# MCU_IMU.net
KiCad netlist of a schematic drawn in Altium Designer
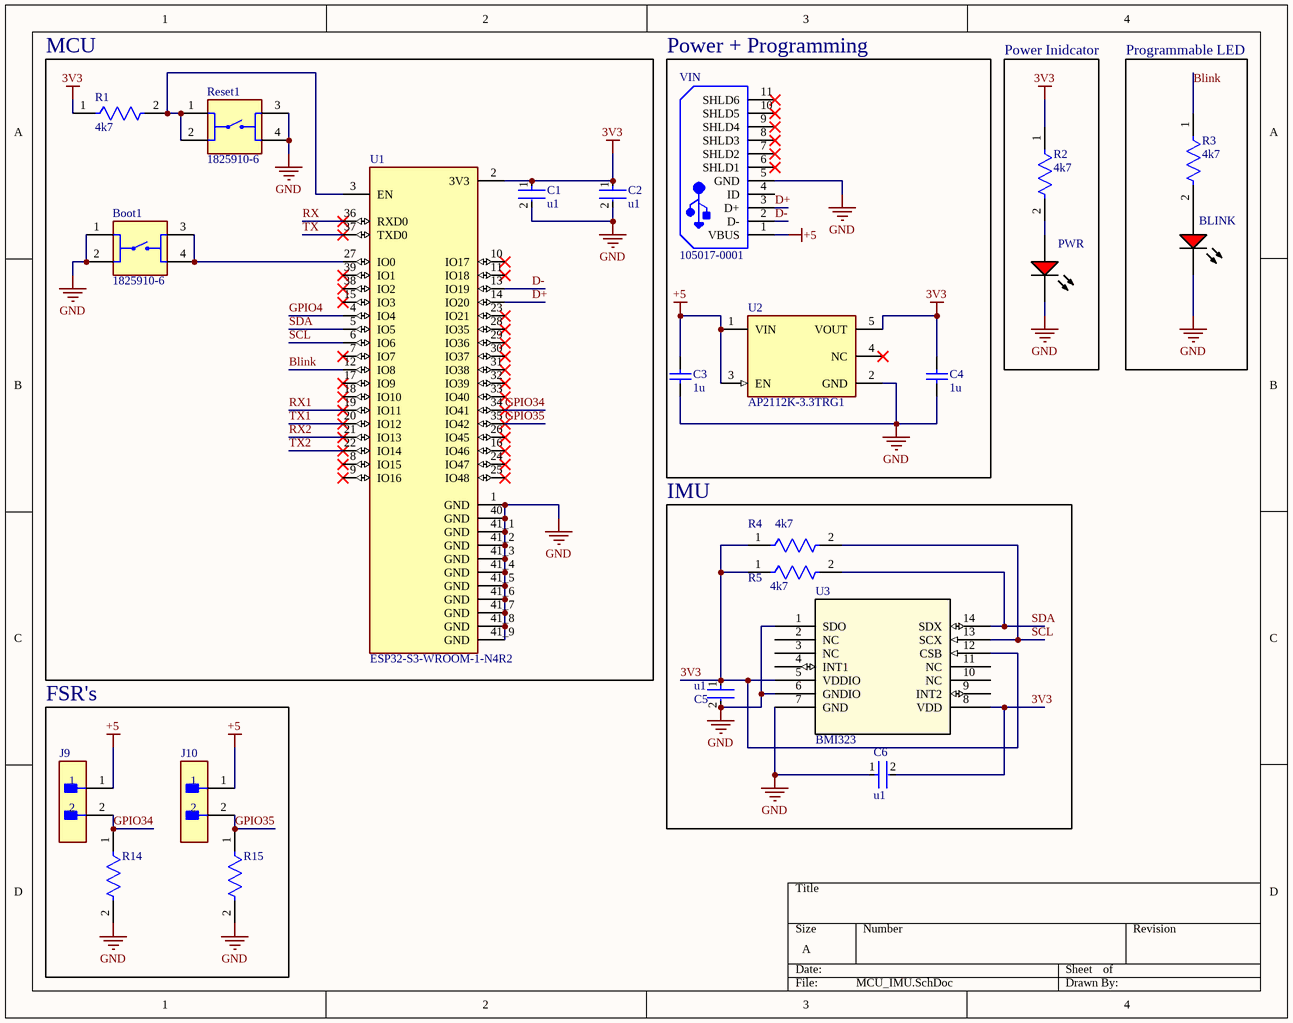
[diagram p0: MCU_IMU.SchDoc]

(export (version "E")
  (design (tool "Eeschema 10.0.6"))
  (components
    (comp (ref "BLINK")
      (value "SML-LX1206IC-TR")
      (footprint "LUMX-SML-LX1206IC_V")
      (description "LED Red, 65 mW, -40 to 85 degC, 2-Pin SMD, RoHS, Tape and Reel")
      (fields (field (name "MANUFACTURER") "Lumex"))
      (libsource (lib "Altium Content Vault") (part "LED-RED-AK-2"))
    )
    (comp (ref "Boot1")
      (value "1825910-6")
      (footprint "SW_1825910-6-4")
      (description "Switch Push Button OFF (ON) SPST Round Button 0.05A 24VDC Momentary Contact PC Pins Thru-Hole")
      (fields (field (name "MF") "TE Connectivity") (field (name "DIGI-KEY_PART_NUMBER") "450-1650-ND"))
      (libsource (lib "First") (part "1825910-6"))
    )
    (comp (ref "C1")
      (value "u1")
      (footprint "FP-CC0805-0_85-MFG")
      (description "CC0805KRX7R9BB104 CAP CER 0.1UF 50V X7R 0805")
      (fields (field (name "TOLERANCE") "0.1") (field (name "MANUFACTURER PART NUMBER") "CC0805KRX7R9BB104"))
      (libsource (lib "Altium Content Vault") (part "11868f565c42a9108669ba33697ecf6"))
    )
    (comp (ref "C2")
      (value "u1")
      (footprint "FP-CC0805-0_85-MFG")
      (description "CC0805KRX7R9BB104 CAP CER 0.1UF 50V X7R 0805")
      (fields (field (name "TOLERANCE") "0.1") (field (name "MANUFACTURER PART NUMBER") "CC0805KRX7R9BB104"))
      (libsource (lib "Altium Content Vault") (part "11868f565c42a9108669ba33697ecf6"))
    )
    (comp (ref "C3")
      (value "1u")
      (footprint "CAPC2013X140X50ML20T25")
      (fields (field (name "MANUFACTURER") "Kemet") (field (name "PART NUMBER") "C0805C105K5RACTU"))
      (libsource (lib "Altium Content Vault") (part "CAP"))
    )
    (comp (ref "C4")
      (value "1u")
      (footprint "CAPC2013X140X50ML20T25")
      (fields (field (name "MANUFACTURER") "Kemet") (field (name "PART NUMBER") "C0805C105K5RACTU"))
      (libsource (lib "Altium Content Vault") (part "CAP"))
    )
    (comp (ref "C5")
      (value "u1")
      (footprint "FP-CC0805-0_85-MFG")
      (description "CC0805KRX7R9BB104 CAP CER 0.1UF 50V X7R 0805")
      (fields (field (name "TOLERANCE") "0.1") (field (name "MANUFACTURER PART NUMBER") "CC0805KRX7R9BB104"))
      (libsource (lib "Altium Content Vault") (part "11868f565c42a9108669ba33697ecf6"))
    )
    (comp (ref "C6")
      (value "u1")
      (footprint "FP-CC0805-0_85-MFG")
      (description "CC0805KRX7R9BB104 CAP CER 0.1UF 50V X7R 0805")
      (fields (field (name "TOLERANCE") "0.1") (field (name "MANUFACTURER PART NUMBER") "CC0805KRX7R9BB104"))
      (libsource (lib "Altium Content Vault") (part "11868f565c42a9108669ba33697ecf6"))
    )
    (comp (ref "J9")
      (value "B2B-XH-A(LF)(SN)")
      (footprint "FP-B2B-XH-A_LF_SN-MFG")
      (description "CONN HEADER VERT 2POS 2.5MM")
      (libsource (lib "Altium Content Vault") (part "3bc925449376181038e59eaffc5286c"))
    )
    (comp (ref "J10")
      (value "B2B-XH-A(LF)(SN)")
      (footprint "FP-B2B-XH-A_LF_SN-MFG")
      (description "CONN HEADER VERT 2POS 2.5MM")
      (libsource (lib "Altium Content Vault") (part "3bc925449376181038e59eaffc5286c"))
    )
    (comp (ref "PWR")
      (value "SML-LX1206IC-TR")
      (footprint "LUMX-SML-LX1206IC_V")
      (description "LED Red, 65 mW, -40 to 85 degC, 2-Pin SMD, RoHS, Tape and Reel")
      (fields (field (name "MANUFACTURER") "Lumex"))
      (libsource (lib "Altium Content Vault") (part "LED-RED-AK-2"))
    )
    (comp (ref "R1")
      (value "4k7")
      (footprint "FP-CRCW0805-e3-IPC_B")
      (description "CRCW08054K70FKEARES Thick Film, 4.7kΩ, 1%, 0.125W, 100ppm/°C, 0805")
      (fields (field (name "TOLERANCE") "1%"))
      (libsource (lib "Altium Content Vault") (part "1029c3af85768c4190bb7ad29bc67b5"))
    )
    (comp (ref "R2")
      (value "4k7")
      (footprint "FP-CRCW0805-e3-IPC_B")
      (description "CRCW08054K70FKEARES Thick Film, 4.7kΩ, 1%, 0.125W, 100ppm/°C, 0805")
      (fields (field (name "TOLERANCE") "1%"))
      (libsource (lib "Altium Content Vault") (part "1029c3af85768c4190bb7ad29bc67b5"))
    )
    (comp (ref "R3")
      (value "4k7")
      (footprint "FP-CRCW0805-e3-IPC_B")
      (description "CRCW08054K70FKEARES Thick Film, 4.7kΩ, 1%, 0.125W, 100ppm/°C, 0805")
      (fields (field (name "TOLERANCE") "1%"))
      (libsource (lib "Altium Content Vault") (part "1029c3af85768c4190bb7ad29bc67b5"))
    )
    (comp (ref "R4")
      (value "4k7")
      (footprint "FP-CRCW0805-e3-IPC_B")
      (description "CRCW08054K70FKEARES Thick Film, 4.7kΩ, 1%, 0.125W, 100ppm/°C, 0805")
      (fields (field (name "TOLERANCE") "1%"))
      (libsource (lib "Altium Content Vault") (part "1029c3af85768c4190bb7ad29bc67b5"))
    )
    (comp (ref "R5")
      (value "4k7")
      (footprint "FP-CRCW0805-e3-IPC_B")
      (description "CRCW08054K70FKEARES Thick Film, 4.7kΩ, 1%, 0.125W, 100ppm/°C, 0805")
      (fields (field (name "TOLERANCE") "1%"))
      (libsource (lib "Altium Content Vault") (part "1029c3af85768c4190bb7ad29bc67b5"))
    )
    (comp (ref "R14")
      (value "RMCF1206FG10K0")
      (footprint "FP-RMCF1206-MFG")
      (description "10kΩ ±1% 0.25W 1206 Thick Film Chip Resistor AEC-Q200 compliant")
      (fields (field (name "TOLERANCE") "1%"))
      (libsource (lib "Altium Content Vault") (part "1029c3af85768c4190bb7ad29bc67b5"))
    )
    (comp (ref "R15")
      (value "RMCF1206FG10K0")
      (footprint "FP-RMCF1206-MFG")
      (description "10kΩ ±1% 0.25W 1206 Thick Film Chip Resistor AEC-Q200 compliant")
      (fields (field (name "TOLERANCE") "1%"))
      (libsource (lib "Altium Content Vault") (part "1029c3af85768c4190bb7ad29bc67b5"))
    )
    (comp (ref "Reset1")
      (value "1825910-6")
      (footprint "SW_1825910-6-4")
      (description "Switch Push Button OFF (ON) SPST Round Button 0.05A 24VDC Momentary Contact PC Pins Thru-Hole")
      (fields (field (name "MF") "TE Connectivity") (field (name "DIGI-KEY_PART_NUMBER") "450-1650-ND"))
      (libsource (lib "First") (part "1825910-6"))
    )
    (comp (ref "U1")
      (value "ESP32-S3-WROOM-1-N4R2")
      (footprint "XCVR_ESP32-S3-WROOM-1-N4R2")
      (description "Bluetooth, WiFi 802.11b/g/n, Bluetooth v5.0 Transceiver Module 2.4GHz PCB Trace Surface Mount")
      (fields (field (name "MF") "Espressif Systems"))
      (libsource (lib "ESP32-S3-WROOM-1-N4R2") (part "ESP32-S3-WROOM-1-N4R2"))
    )
    (comp (ref "U2")
      (value "AP2112K-3.3TRG1")
      (footprint "FP-SOT25-IPC_A")
      (description "IC REG LINEAR 3.3V 600MA SOT25")
      (libsource (lib "Altium Content Vault") (part "c8ab751aee5229183125ab046a11caa"))
    )
    (comp (ref "U3")
      (value "BMI323")
      (footprint "BMI323_BOS")
      (description "No Description Available")
      (fields (field (name "COPYRIGHT") "Copyright (C) 2025 Ultra Librarian. All rights reserved."))
      (libsource (lib "AI_Project_Library") (part "BMI323"))
    )
    (comp (ref "VIN")
      (value "105017-0001")
      (footprint "USB-MICRO-B_V")
      (fields (field (name "MANUFACTURER") "Molex"))
      (libsource (lib "Altium Content Vault") (part "USB-5-6SHLD"))
    )
  )
  (nets
    (net (code "1") (name "+5") (class "Default")
      (node (ref "C3") (pin "2") (pinfunction "2_2") (pintype "passive"))
      (node (ref "J10") (pin "1") (pinfunction "1_1") (pintype "passive"))
      (node (ref "J9") (pin "1") (pinfunction "1_1") (pintype "passive"))
      (node (ref "U2") (pin "1") (pinfunction "VIN_1") (pintype "power_in"))
      (node (ref "U2") (pin "3") (pinfunction "EN_3") (pintype "input"))
      (node (ref "VIN") (pin "1") (pinfunction "VBUS_1") (pintype "passive"))
    )
    (net (code "2") (name "/Blink") (class "Default")
      (node (ref "R3") (pin "1") (pinfunction "1_1") (pintype "passive"))
      (node (ref "U1") (pin "12") (pinfunction "IO8_12") (pintype "bidirectional"))
    )
    (net (code "3") (name "/D+") (class "Default")
      (node (ref "U1") (pin "14") (pinfunction "IO20_14") (pintype "bidirectional"))
      (node (ref "VIN") (pin "3") (pinfunction "D+_3") (pintype "passive"))
    )
    (net (code "4") (name "/D-") (class "Default")
      (node (ref "U1") (pin "13") (pinfunction "IO19_13") (pintype "bidirectional"))
      (node (ref "VIN") (pin "2") (pinfunction "D-_2") (pintype "passive"))
    )
    (net (code "5") (name "/GPIO4") (class "Default")
      (node (ref "U1") (pin "4") (pinfunction "IO4_4") (pintype "bidirectional"))
    )
    (net (code "6") (name "/GPIO34") (class "Default")
      (node (ref "J9") (pin "2") (pinfunction "2_2") (pintype "passive"))
      (node (ref "R14") (pin "1") (pinfunction "1_1") (pintype "passive"))
      (node (ref "U1") (pin "34") (pinfunction "IO41_34") (pintype "bidirectional"))
    )
    (net (code "7") (name "/GPIO35") (class "Default")
      (node (ref "J10") (pin "2") (pinfunction "2_2") (pintype "passive"))
      (node (ref "R15") (pin "1") (pinfunction "1_1") (pintype "passive"))
      (node (ref "U1") (pin "35") (pinfunction "IO42_35") (pintype "bidirectional"))
    )
    (net (code "8") (name "/RX") (class "Default")
      (node (ref "U1") (pin "36") (pinfunction "RXD0_36") (pintype "bidirectional+no_connect"))
    )
    (net (code "9") (name "/RX1") (class "Default")
      (node (ref "U1") (pin "19") (pinfunction "IO11_19") (pintype "bidirectional+no_connect"))
    )
    (net (code "10") (name "/RX2") (class "Default")
      (node (ref "U1") (pin "21") (pinfunction "IO13_21") (pintype "bidirectional+no_connect"))
    )
    (net (code "11") (name "/SCL") (class "Default")
      (node (ref "R4") (pin "2") (pinfunction "2_2") (pintype "passive"))
      (node (ref "U1") (pin "6") (pinfunction "IO6_6") (pintype "bidirectional"))
      (node (ref "U3") (pin "13") (pinfunction "SCX_13") (pintype "input"))
    )
    (net (code "12") (name "/SDA") (class "Default")
      (node (ref "R5") (pin "2") (pinfunction "2_2") (pintype "passive"))
      (node (ref "U1") (pin "5") (pinfunction "IO5_5") (pintype "bidirectional"))
      (node (ref "U3") (pin "14") (pinfunction "SDX_14") (pintype "bidirectional"))
    )
    (net (code "13") (name "/TX") (class "Default")
      (node (ref "U1") (pin "37") (pinfunction "TXD0_37") (pintype "bidirectional+no_connect"))
    )
    (net (code "14") (name "/TX1") (class "Default")
      (node (ref "U1") (pin "20") (pinfunction "IO12_20") (pintype "bidirectional+no_connect"))
    )
    (net (code "15") (name "/TX2") (class "Default")
      (node (ref "U1") (pin "22") (pinfunction "IO14_22") (pintype "bidirectional+no_connect"))
    )
    (net (code "16") (name "3V3") (class "Default")
      (node (ref "C1") (pin "1") (pinfunction "1_1") (pintype "passive"))
      (node (ref "C2") (pin "1") (pinfunction "1_1") (pintype "passive"))
      (node (ref "C4") (pin "2") (pinfunction "2_2") (pintype "passive"))
      (node (ref "C5") (pin "1") (pinfunction "1_1") (pintype "passive"))
      (node (ref "C6") (pin "2") (pinfunction "2_2") (pintype "passive"))
      (node (ref "R1") (pin "1") (pinfunction "1_1") (pintype "passive"))
      (node (ref "R2") (pin "1") (pinfunction "1_1") (pintype "passive"))
      (node (ref "R4") (pin "1") (pinfunction "1_1") (pintype "passive"))
      (node (ref "R5") (pin "1") (pinfunction "1_1") (pintype "passive"))
      (node (ref "U1") (pin "2") (pinfunction "3V3_2") (pintype "power_in"))
      (node (ref "U2") (pin "5") (pinfunction "VOUT_5") (pintype "power_in"))
      (node (ref "U3") (pin "12") (pinfunction "CSB_12") (pintype "input"))
      (node (ref "U3") (pin "5") (pinfunction "VDDIO_5") (pintype "power_in"))
      (node (ref "U3") (pin "8") (pinfunction "VDD_8") (pintype "power_in"))
    )
    (net (code "17") (name "GND") (class "Default")
      (node (ref "BLINK") (pin "2") (pinfunction "K_2") (pintype "passive"))
      (node (ref "Boot1") (pin "1") (pinfunction "1_1") (pintype "passive"))
      (node (ref "Boot1") (pin "2") (pinfunction "2_2") (pintype "passive"))
      (node (ref "C1") (pin "2") (pinfunction "2_2") (pintype "passive"))
      (node (ref "C2") (pin "2") (pinfunction "2_2") (pintype "passive"))
      (node (ref "C3") (pin "1") (pinfunction "1_1") (pintype "passive"))
      (node (ref "C4") (pin "1") (pinfunction "1_1") (pintype "passive"))
      (node (ref "C5") (pin "2") (pinfunction "2_2") (pintype "passive"))
      (node (ref "C6") (pin "1") (pinfunction "1_1") (pintype "passive"))
      (node (ref "PWR") (pin "2") (pinfunction "K_2") (pintype "passive"))
      (node (ref "R14") (pin "2") (pinfunction "2_2") (pintype "passive"))
      (node (ref "R15") (pin "2") (pinfunction "2_2") (pintype "passive"))
      (node (ref "Reset1") (pin "3") (pinfunction "3_3") (pintype "passive"))
      (node (ref "Reset1") (pin "4") (pinfunction "4_4") (pintype "passive"))
      (node (ref "U1") (pin "1") (pinfunction "GND_1") (pintype "power_in"))
      (node (ref "U1") (pin "40") (pinfunction "GND_40") (pintype "power_in"))
      (node (ref "U1") (pin "41_1") (pinfunction "GND_41_1") (pintype "power_in"))
      (node (ref "U1") (pin "41_2") (pinfunction "GND_41_2") (pintype "power_in"))
      (node (ref "U1") (pin "41_3") (pinfunction "GND_41_3") (pintype "power_in"))
      (node (ref "U1") (pin "41_4") (pinfunction "GND_41_4") (pintype "power_in"))
      (node (ref "U1") (pin "41_5") (pinfunction "GND_41_5") (pintype "power_in"))
      (node (ref "U1") (pin "41_6") (pinfunction "GND_41_6") (pintype "power_in"))
      (node (ref "U1") (pin "41_7") (pinfunction "GND_41_7") (pintype "power_in"))
      (node (ref "U1") (pin "41_8") (pinfunction "GND_41_8") (pintype "power_in"))
      (node (ref "U1") (pin "41_9") (pinfunction "GND_41_9") (pintype "power_in"))
      (node (ref "U2") (pin "2") (pinfunction "GND_2") (pintype "power_in"))
      (node (ref "U3") (pin "1") (pinfunction "SDO_1") (pintype "passive"))
      (node (ref "U3") (pin "6") (pinfunction "GNDIO_6") (pintype "power_in"))
      (node (ref "U3") (pin "7") (pinfunction "GND_7") (pintype "power_in"))
      (node (ref "VIN") (pin "5") (pinfunction "GND_5") (pintype "passive"))
    )
    (net (code "18") (name "Net-(BLINK-A)") (class "Default")
      (node (ref "BLINK") (pin "1") (pinfunction "A_1") (pintype "passive"))
      (node (ref "R3") (pin "2") (pinfunction "2_2") (pintype "passive"))
    )
    (net (code "19") (name "Net-(PWR-A)") (class "Default")
      (node (ref "PWR") (pin "1") (pinfunction "A_1") (pintype "passive"))
      (node (ref "R2") (pin "2") (pinfunction "2_2") (pintype "passive"))
    )
    (net (code "20") (name "Net-(U1-EN)") (class "Default")
      (node (ref "R1") (pin "2") (pinfunction "2_2") (pintype "passive"))
      (node (ref "Reset1") (pin "1") (pinfunction "1_1") (pintype "passive"))
      (node (ref "Reset1") (pin "2") (pinfunction "2_2") (pintype "passive"))
      (node (ref "U1") (pin "3") (pinfunction "EN_3") (pintype "power_in"))
    )
    (net (code "21") (name "Net-(U1-IO0)") (class "Default")
      (node (ref "Boot1") (pin "3") (pinfunction "3_3") (pintype "passive"))
      (node (ref "Boot1") (pin "4") (pinfunction "4_4") (pintype "passive"))
      (node (ref "U1") (pin "27") (pinfunction "IO0_27") (pintype "bidirectional"))
    )
    (net (code "22") (name "unconnected-(U1-IO1-Pad39)") (class "Default")
      (node (ref "U1") (pin "39") (pinfunction "IO1_39") (pintype "bidirectional+no_connect"))
    )
    (net (code "23") (name "unconnected-(U1-IO2-Pad38)") (class "Default")
      (node (ref "U1") (pin "38") (pinfunction "IO2_38") (pintype "bidirectional+no_connect"))
    )
    (net (code "24") (name "unconnected-(U1-IO3-Pad15)") (class "Default")
      (node (ref "U1") (pin "15") (pinfunction "IO3_15") (pintype "bidirectional+no_connect"))
    )
    (net (code "25") (name "unconnected-(U1-IO7-Pad7)") (class "Default")
      (node (ref "U1") (pin "7") (pinfunction "IO7_7") (pintype "bidirectional+no_connect"))
    )
    (net (code "26") (name "unconnected-(U1-IO9-Pad17)") (class "Default")
      (node (ref "U1") (pin "17") (pinfunction "IO9_17") (pintype "bidirectional+no_connect"))
    )
    (net (code "27") (name "unconnected-(U1-IO10-Pad18)") (class "Default")
      (node (ref "U1") (pin "18") (pinfunction "IO10_18") (pintype "bidirectional+no_connect"))
    )
    (net (code "28") (name "unconnected-(U1-IO15-Pad8)") (class "Default")
      (node (ref "U1") (pin "8") (pinfunction "IO15_8") (pintype "bidirectional+no_connect"))
    )
    (net (code "29") (name "unconnected-(U1-IO16-Pad9)") (class "Default")
      (node (ref "U1") (pin "9") (pinfunction "IO16_9") (pintype "bidirectional+no_connect"))
    )
    (net (code "30") (name "unconnected-(U1-IO17-Pad10)") (class "Default")
      (node (ref "U1") (pin "10") (pinfunction "IO17_10") (pintype "bidirectional+no_connect"))
    )
    (net (code "31") (name "unconnected-(U1-IO18-Pad11)") (class "Default")
      (node (ref "U1") (pin "11") (pinfunction "IO18_11") (pintype "bidirectional+no_connect"))
    )
    (net (code "32") (name "unconnected-(U1-IO21-Pad23)") (class "Default")
      (node (ref "U1") (pin "23") (pinfunction "IO21_23") (pintype "bidirectional+no_connect"))
    )
    (net (code "33") (name "unconnected-(U1-IO35-Pad28)") (class "Default")
      (node (ref "U1") (pin "28") (pinfunction "IO35_28") (pintype "bidirectional+no_connect"))
    )
    (net (code "34") (name "unconnected-(U1-IO36-Pad29)") (class "Default")
      (node (ref "U1") (pin "29") (pinfunction "IO36_29") (pintype "bidirectional+no_connect"))
    )
    (net (code "35") (name "unconnected-(U1-IO37-Pad30)") (class "Default")
      (node (ref "U1") (pin "30") (pinfunction "IO37_30") (pintype "bidirectional+no_connect"))
    )
    (net (code "36") (name "unconnected-(U1-IO38-Pad31)") (class "Default")
      (node (ref "U1") (pin "31") (pinfunction "IO38_31") (pintype "bidirectional+no_connect"))
    )
    (net (code "37") (name "unconnected-(U1-IO39-Pad32)") (class "Default")
      (node (ref "U1") (pin "32") (pinfunction "IO39_32") (pintype "bidirectional+no_connect"))
    )
    (net (code "38") (name "unconnected-(U1-IO40-Pad33)") (class "Default")
      (node (ref "U1") (pin "33") (pinfunction "IO40_33") (pintype "bidirectional+no_connect"))
    )
    (net (code "39") (name "unconnected-(U1-IO45-Pad26)") (class "Default")
      (node (ref "U1") (pin "26") (pinfunction "IO45_26") (pintype "bidirectional+no_connect"))
    )
    (net (code "40") (name "unconnected-(U1-IO46-Pad16)") (class "Default")
      (node (ref "U1") (pin "16") (pinfunction "IO46_16") (pintype "bidirectional+no_connect"))
    )
    (net (code "41") (name "unconnected-(U1-IO47-Pad24)") (class "Default")
      (node (ref "U1") (pin "24") (pinfunction "IO47_24") (pintype "bidirectional+no_connect"))
    )
    (net (code "42") (name "unconnected-(U1-IO48-Pad25)") (class "Default")
      (node (ref "U1") (pin "25") (pinfunction "IO48_25") (pintype "bidirectional+no_connect"))
    )
    (net (code "43") (name "unconnected-(U2-NC-Pad4)") (class "Default")
      (node (ref "U2") (pin "4") (pinfunction "NC_4") (pintype "passive+no_connect"))
    )
    (net (code "44") (name "unconnected-(U3-INT1-Pad4)") (class "Default")
      (node (ref "U3") (pin "4") (pinfunction "INT1_4") (pintype "bidirectional"))
    )
    (net (code "45") (name "unconnected-(U3-INT2-Pad9)") (class "Default")
      (node (ref "U3") (pin "9") (pinfunction "INT2_9") (pintype "bidirectional"))
    )
    (net (code "46") (name "unconnected-(U3-NC-Pad2)") (class "Default")
      (node (ref "U3") (pin "2") (pinfunction "NC_2") (pintype "passive"))
    )
    (net (code "47") (name "unconnected-(U3-NC-Pad3)") (class "Default")
      (node (ref "U3") (pin "3") (pinfunction "NC_3") (pintype "passive"))
    )
    (net (code "48") (name "unconnected-(U3-NC-Pad10)") (class "Default")
      (node (ref "U3") (pin "10") (pinfunction "NC_10") (pintype "passive"))
    )
    (net (code "49") (name "unconnected-(U3-NC-Pad11)") (class "Default")
      (node (ref "U3") (pin "11") (pinfunction "NC_11") (pintype "passive"))
    )
    (net (code "50") (name "unconnected-(VIN-ID-Pad4)") (class "Default")
      (node (ref "VIN") (pin "4") (pinfunction "ID_4") (pintype "passive"))
    )
    (net (code "51") (name "unconnected-(VIN-SHLD1-Pad6)") (class "Default")
      (node (ref "VIN") (pin "6") (pinfunction "SHLD1_6") (pintype "passive+no_connect"))
    )
    (net (code "52") (name "unconnected-(VIN-SHLD2-Pad7)") (class "Default")
      (node (ref "VIN") (pin "7") (pinfunction "SHLD2_7") (pintype "passive+no_connect"))
    )
    (net (code "53") (name "unconnected-(VIN-SHLD3-Pad8)") (class "Default")
      (node (ref "VIN") (pin "8") (pinfunction "SHLD3_8") (pintype "passive+no_connect"))
    )
    (net (code "54") (name "unconnected-(VIN-SHLD4-Pad9)") (class "Default")
      (node (ref "VIN") (pin "9") (pinfunction "SHLD4_9") (pintype "passive+no_connect"))
    )
    (net (code "55") (name "unconnected-(VIN-SHLD5-Pad10)") (class "Default")
      (node (ref "VIN") (pin "10") (pinfunction "SHLD5_10") (pintype "passive+no_connect"))
    )
    (net (code "56") (name "unconnected-(VIN-SHLD6-Pad11)") (class "Default")
      (node (ref "VIN") (pin "11") (pinfunction "SHLD6_11") (pintype "passive+no_connect"))
    )
  )
)
